# NEWSWEEP.net
KiCad netlist of a schematic drawn in Altium Designer
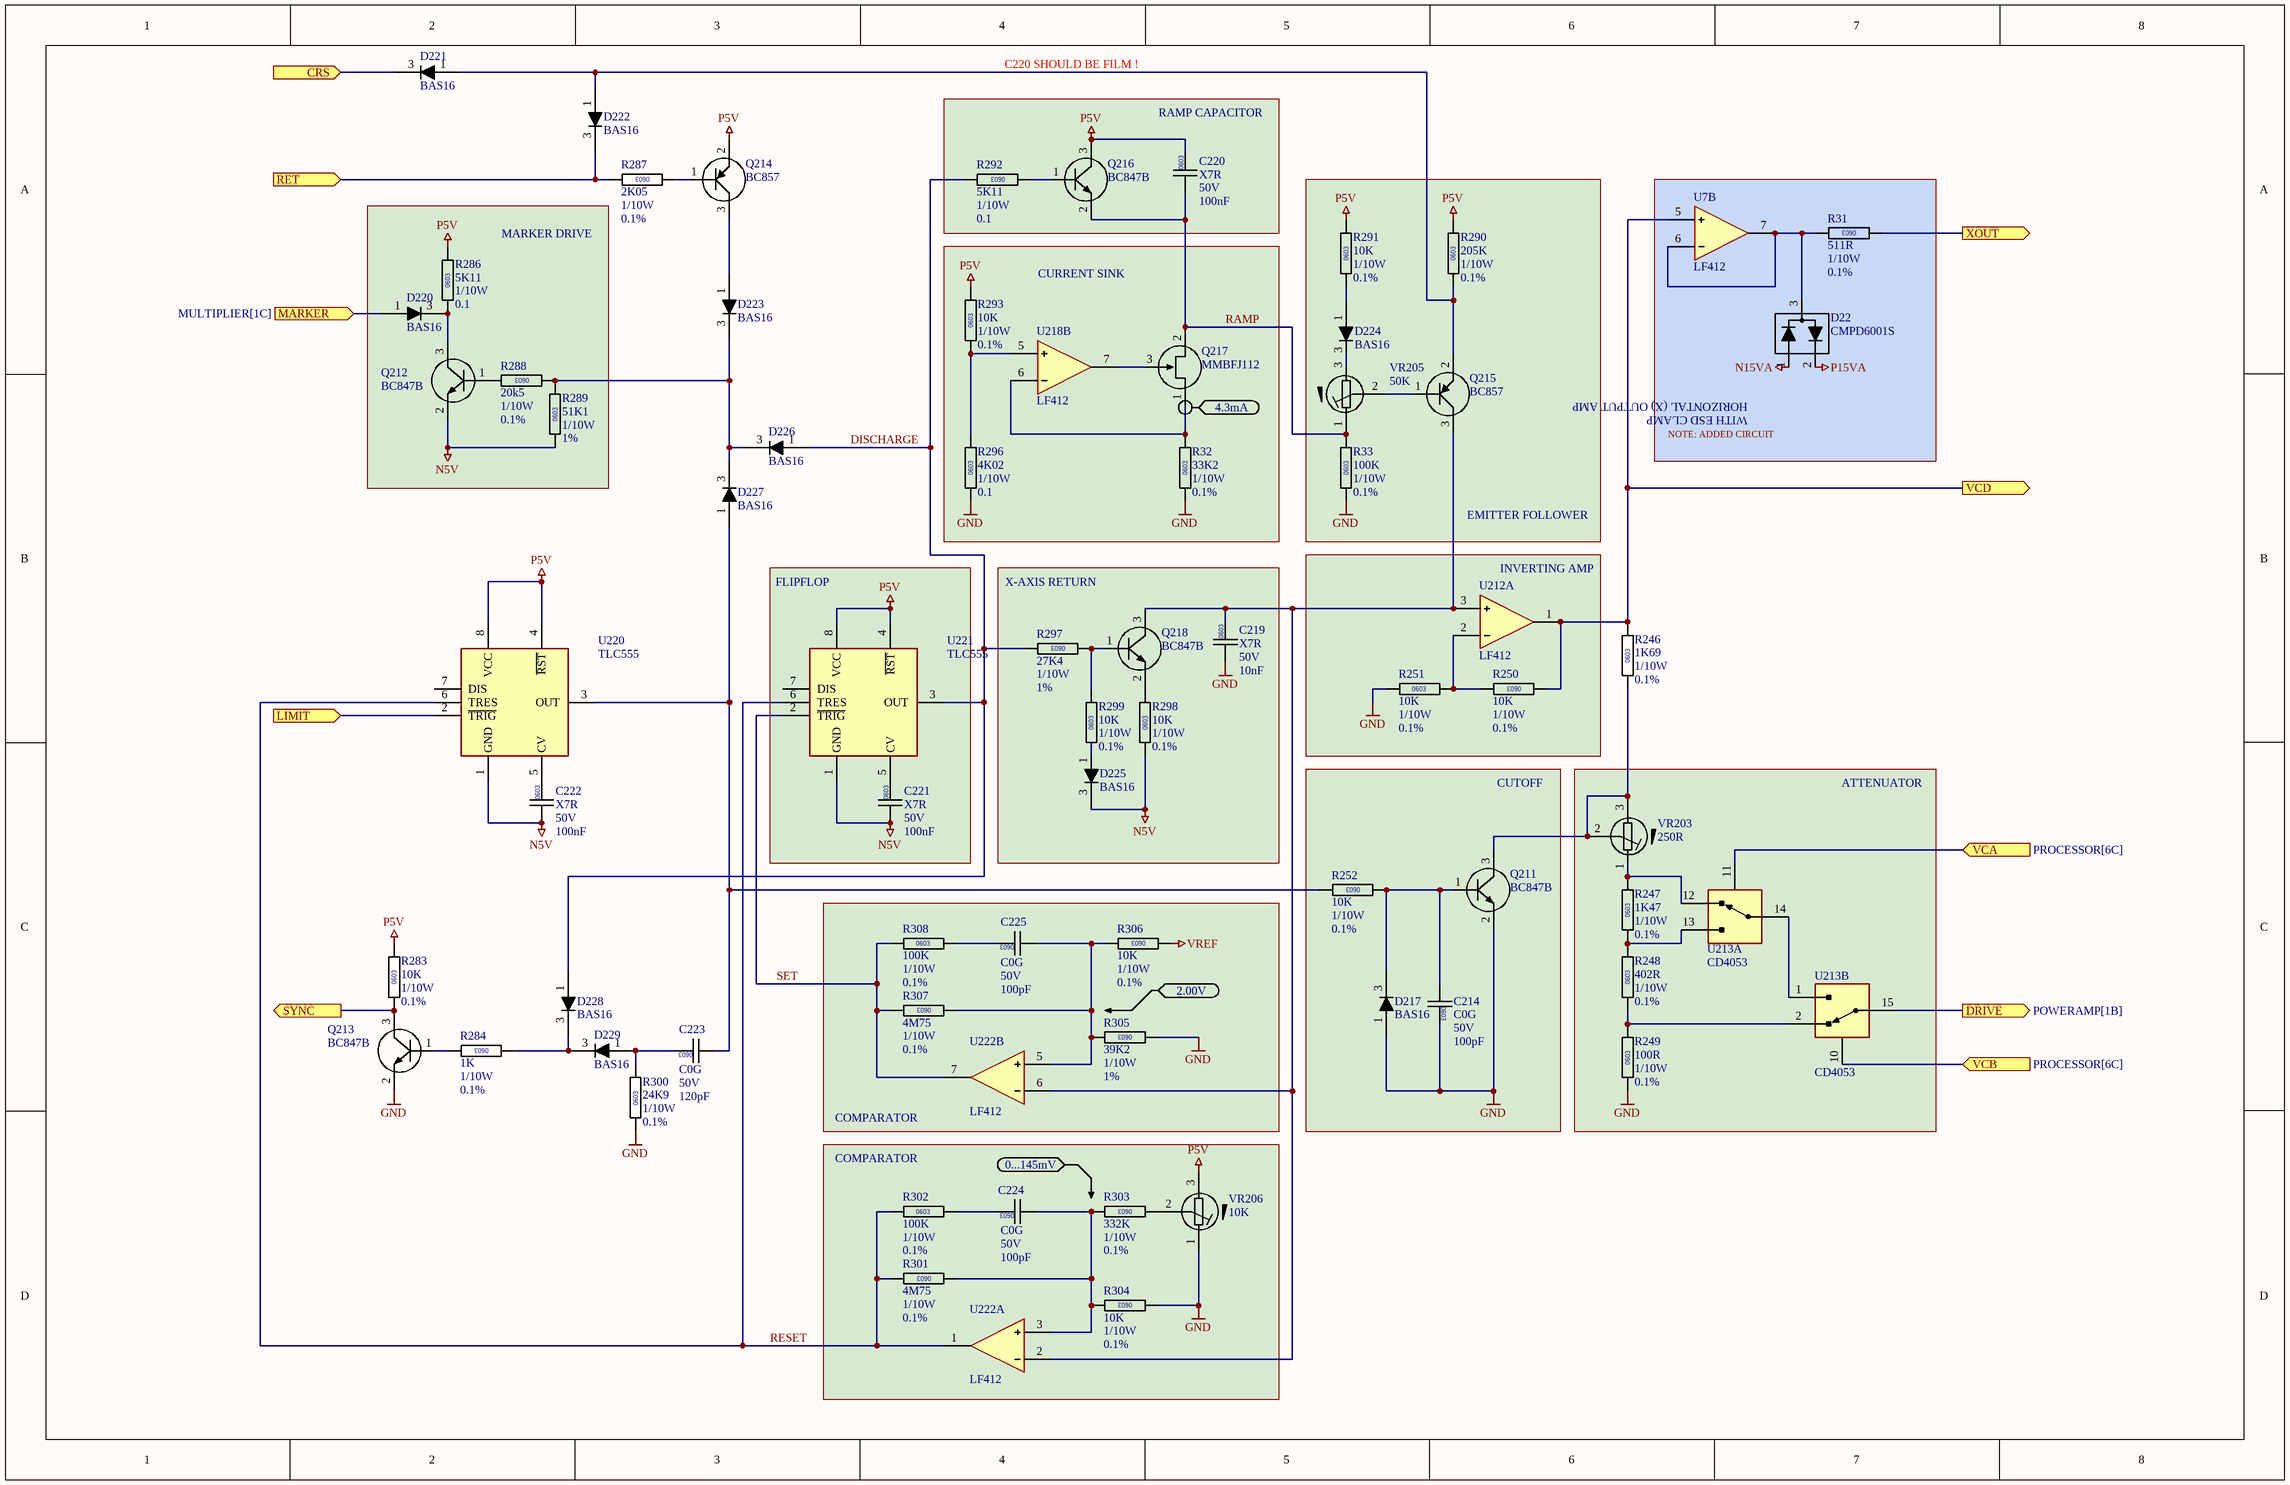
[diagram p0: NEWSWEEP.SchDoc]

(export (version "E")
  (design (tool "Eeschema 10.0.6"))
  (components
    (comp (ref "C214")
      (value "CAP0603")
      (footprint "CAPC0603")
      (description "CAPACITOR,CERAMIC,100pF,50V,C0G,0603")
      (fields
        (field (name "DIELECTRIC") "C0G")
        (field (name "VOLTAGE") "50V")
        (field (name "CAPACITANCE") "100pF")
      )
      (libsource (lib "CAPACITORS") (part "CAPC-0603-100pF-50V-C0G"))
    )
    (comp (ref "C219")
      (value "CAP0603")
      (footprint "CAPC0603")
      (description "CAPACITOR,CERAMIC,10nF,50V,X7R,0603")
      (fields
        (field (name "DIELECTRIC") "X7R")
        (field (name "VOLTAGE") "50V")
        (field (name "CAPACITANCE") "10nF")
      )
      (libsource (lib "CAPACITORS") (part "CAPC-0603-10nF-50V-X7R"))
    )
    (comp (ref "C220")
      (value "CAP0603")
      (footprint "CAPC0603")
      (description "CAPACITOR,CERAMIC,100nF,50V,X7R,0603")
      (fields
        (field (name "DIELECTRIC") "X7R")
        (field (name "VOLTAGE") "50V")
        (field (name "CAPACITANCE") "100nF")
      )
      (libsource (lib "CAPACITORS") (part "CAPC-0603-100nF-50V-X7R"))
    )
    (comp (ref "C221")
      (value "CAP0603")
      (footprint "CAPC0603")
      (description "CAPACITOR,CERAMIC,100nF,50V,X7R,0603")
      (fields
        (field (name "DIELECTRIC") "X7R")
        (field (name "VOLTAGE") "50V")
        (field (name "CAPACITANCE") "100nF")
      )
      (libsource (lib "CAPACITORS") (part "CAPC-0603-100nF-50V-X7R"))
    )
    (comp (ref "C222")
      (value "CAP0603")
      (footprint "CAPC0603")
      (description "CAPACITOR,CERAMIC,100nF,50V,X7R,0603")
      (fields
        (field (name "DIELECTRIC") "X7R")
        (field (name "VOLTAGE") "50V")
        (field (name "CAPACITANCE") "100nF")
      )
      (libsource (lib "CAPACITORS") (part "CAPC-0603-100nF-50V-X7R"))
    )
    (comp (ref "C223")
      (value "CAP0603")
      (footprint "CAPC0603")
      (description "CAPACITOR,CERAMIC,120pF,50V,C0G,0603")
      (fields
        (field (name "DIELECTRIC") "C0G")
        (field (name "VOLTAGE") "50V")
        (field (name "CAPACITANCE") "120pF")
      )
      (libsource (lib "CAPACITORS") (part "CAPC-0603-120pF-50V-C0G"))
    )
    (comp (ref "C224")
      (value "CAP0603")
      (footprint "CAPC0603")
      (description "CAPACITOR,CERAMIC,100pF,50V,C0G,0603")
      (fields
        (field (name "DIELECTRIC") "C0G")
        (field (name "VOLTAGE") "50V")
        (field (name "CAPACITANCE") "100pF")
      )
      (libsource (lib "CAPACITORS") (part "CAPC-0603-100pF-50V-C0G"))
    )
    (comp (ref "C225")
      (value "CAP0603")
      (footprint "CAPC0603")
      (description "CAPACITOR,CERAMIC,100pF,50V,C0G,0603")
      (fields
        (field (name "DIELECTRIC") "C0G")
        (field (name "VOLTAGE") "50V")
        (field (name "CAPACITANCE") "100pF")
      )
      (libsource (lib "CAPACITORS") (part "CAPC-0603-100pF-50V-C0G"))
    )
    (comp (ref "D22")
      (value "CMPD6001S")
      (footprint "SOT23")
      (description "DIODE,75V,250mA,SOT23,500pA ULTRA LOW LEAKAGE")
      (libsource (lib "DIODES") (part "DIODE-CENTRALSEMI-CMPD6001S"))
    )
    (comp (ref "D217")
      (value "BAS16")
      (description "DIODE,RECTIFIER,75V,0.3A,BAS16,SOT23")
      (libsource (lib "DIODES") (part "DIODE-RECTIFIER-DIODES-BAS16-SOT23"))
    )
    (comp (ref "D220")
      (value "BAS16")
      (description "DIODE,RECTIFIER,75V,0.3A,BAS16,SOT23")
      (libsource (lib "DIODES") (part "DIODE-RECTIFIER-DIODES-BAS16-SOT23"))
    )
    (comp (ref "D221")
      (value "BAS16")
      (description "DIODE,RECTIFIER,75V,0.3A,BAS16,SOT23")
      (libsource (lib "DIODES") (part "DIODE-RECTIFIER-DIODES-BAS16-SOT23"))
    )
    (comp (ref "D222")
      (value "BAS16")
      (description "DIODE,RECTIFIER,75V,0.3A,BAS16,SOT23")
      (libsource (lib "DIODES") (part "DIODE-RECTIFIER-DIODES-BAS16-SOT23"))
    )
    (comp (ref "D223")
      (value "BAS16")
      (description "DIODE,RECTIFIER,75V,0.3A,BAS16,SOT23")
      (libsource (lib "DIODES") (part "DIODE-RECTIFIER-DIODES-BAS16-SOT23"))
    )
    (comp (ref "D224")
      (value "BAS16")
      (description "DIODE,RECTIFIER,75V,0.3A,BAS16,SOT23")
      (libsource (lib "DIODES") (part "DIODE-RECTIFIER-DIODES-BAS16-SOT23"))
    )
    (comp (ref "D225")
      (value "BAS16")
      (description "DIODE,RECTIFIER,75V,0.3A,BAS16,SOT23")
      (libsource (lib "DIODES") (part "DIODE-RECTIFIER-DIODES-BAS16-SOT23"))
    )
    (comp (ref "D226")
      (value "BAS16")
      (description "DIODE,RECTIFIER,75V,0.3A,BAS16,SOT23")
      (libsource (lib "DIODES") (part "DIODE-RECTIFIER-DIODES-BAS16-SOT23"))
    )
    (comp (ref "D227")
      (value "BAS16")
      (description "DIODE,RECTIFIER,75V,0.3A,BAS16,SOT23")
      (libsource (lib "DIODES") (part "DIODE-RECTIFIER-DIODES-BAS16-SOT23"))
    )
    (comp (ref "D228")
      (value "BAS16")
      (description "DIODE,RECTIFIER,75V,0.3A,BAS16,SOT23")
      (libsource (lib "DIODES") (part "DIODE-RECTIFIER-DIODES-BAS16-SOT23"))
    )
    (comp (ref "D229")
      (value "BAS16")
      (description "DIODE,RECTIFIER,75V,0.3A,BAS16,SOT23")
      (libsource (lib "DIODES") (part "DIODE-RECTIFIER-DIODES-BAS16-SOT23"))
    )
    (comp (ref "Q211")
      (value "BC847B")
      (footprint "SOT23")
      (description "XSTR,NPN,45V,0.1A,,BC847B,SOT23")
      (libsource (lib "TRANSISTORS") (part "XSTR-NPN-BC847"))
    )
    (comp (ref "Q212")
      (value "BC847B")
      (footprint "SOT23")
      (description "XSTR,NPN,45V,0.1A,,BC847B,SOT23")
      (libsource (lib "TRANSISTORS") (part "XSTR-NPN-BC847"))
    )
    (comp (ref "Q213")
      (value "BC847B")
      (footprint "SOT23")
      (description "XSTR,NPN,45V,0.1A,,BC847B,SOT23")
      (libsource (lib "TRANSISTORS") (part "XSTR-NPN-BC847"))
    )
    (comp (ref "Q214")
      (value "BC857")
      (footprint "SOT23")
      (description "XSTR,PNP,SOT23,BC857,SOT23")
      (libsource (lib "TRANSISTORS") (part "XSTR-PNP-BC857"))
    )
    (comp (ref "Q215")
      (value "BC857")
      (footprint "SOT23")
      (description "XSTR,PNP,SOT23,BC857,SOT23")
      (libsource (lib "TRANSISTORS") (part "XSTR-PNP-BC857"))
    )
    (comp (ref "Q216")
      (value "BC847B")
      (footprint "SOT23")
      (description "XSTR,NPN,45V,0.1A,,BC847B,SOT23")
      (libsource (lib "TRANSISTORS") (part "XSTR-NPN-BC847"))
    )
    (comp (ref "Q217")
      (value "MMBFJ112")
      (description "XSTR,JFET,NCHAN,ONSEMI,MMBFJ112,SOT23")
      (libsource (lib "TRANSISTORS") (part "XSTR-ONSEMI-J112-SOT23"))
    )
    (comp (ref "Q218")
      (value "BC847B")
      (footprint "SOT23")
      (description "XSTR,NPN,45V,0.1A,,BC847B,SOT23")
      (libsource (lib "TRANSISTORS") (part "XSTR-NPN-BC847"))
    )
    (comp (ref "R31")
      (value "511R")
      (footprint "RESC0603")
      (description "RESISTOR,511R,0.1%,100mW,0603 (1608)")
      (fields
        (field (name "POWER") "1/10W")
        (field (name "TOLERANCE") "0.1%")
        (field (name "Comment") "RESC0603")
      )
      (libsource (lib "RESISTORS") (part "RESC-0603-511R-0.1%"))
    )
    (comp (ref "R32")
      (value "33K2")
      (footprint "RESC0603")
      (description "RESISTOR,33K2,0.1%,100mW,0603 (1608)")
      (fields
        (field (name "POWER") "1/10W")
        (field (name "TOLERANCE") "0.1%")
        (field (name "Comment") "RESC0603")
      )
      (libsource (lib "RESISTORS") (part "RESC-0603-33K2-0.1%-1/10W"))
    )
    (comp (ref "R33")
      (value "100K")
      (footprint "RESC0603")
      (description "RESISTOR,100K,0.1%,100mW,0603 (1608)")
      (fields
        (field (name "POWER") "1/10W")
        (field (name "TOLERANCE") "0.1%")
        (field (name "Comment") "RESC0603")
      )
      (libsource (lib "RESISTORS") (part "RESC-0603-100K-0.1%-1/10W"))
    )
    (comp (ref "R246")
      (value "1K69")
      (footprint "RESC0603")
      (description "RESISTOR,1K69,0.1%,100mW,0603 (1608)")
      (fields
        (field (name "POWER") "1/10W")
        (field (name "TOLERANCE") "0.1%")
        (field (name "Comment") "RESC0603")
      )
      (libsource (lib "RESISTORS") (part "RESC-0603-1K69-0.1%-1/10W"))
    )
    (comp (ref "R247")
      (value "1K47")
      (footprint "RESC0603")
      (description "RESISTOR,1K47,0.1%,100mW,0603 (1608)")
      (fields
        (field (name "POWER") "1/10W")
        (field (name "TOLERANCE") "0.1%")
        (field (name "Comment") "RESC0603")
      )
      (libsource (lib "RESISTORS") (part "RESC-0603-1K47-0.1%-1/10W"))
    )
    (comp (ref "R248")
      (value "402R")
      (footprint "RESC0603")
      (description "RESISTOR,402R,0.1%,100mW,0603 (1608)")
      (fields
        (field (name "POWER") "1/10W")
        (field (name "TOLERANCE") "0.1%")
        (field (name "Comment") "RESC0603")
      )
      (libsource (lib "RESISTORS") (part "RESC-0603-402R-0.1%-1/10W"))
    )
    (comp (ref "R249")
      (value "100R")
      (footprint "RESC0603")
      (description "RESISTOR,100R,0.1%,100mW,0603 (1608)")
      (fields
        (field (name "POWER") "1/10W")
        (field (name "TOLERANCE") "0.1%")
        (field (name "Comment") "RESC0603")
      )
      (libsource (lib "RESISTORS") (part "RESC-0603-100R,0.1%-1/10W"))
    )
    (comp (ref "R250")
      (value "10K")
      (footprint "RESC0603")
      (description "RESISTOR,10K,0.1%,100mW,0603 (1608)")
      (fields
        (field (name "POWER") "1/10W")
        (field (name "TOLERANCE") "0.1%")
        (field (name "Comment") "RESC0603")
      )
      (libsource (lib "RESISTORS") (part "RESC-0603-10K-0.1%-1/10W"))
    )
    (comp (ref "R251")
      (value "10K")
      (footprint "RESC0603")
      (description "RESISTOR,10K,0.1%,100mW,0603 (1608)")
      (fields
        (field (name "POWER") "1/10W")
        (field (name "TOLERANCE") "0.1%")
        (field (name "Comment") "RESC0603")
      )
      (libsource (lib "RESISTORS") (part "RESC-0603-10K-0.1%-1/10W"))
    )
    (comp (ref "R252")
      (value "10K")
      (footprint "RESC0603")
      (description "RESISTOR,10K,0.1%,100mW,0603 (1608)")
      (fields
        (field (name "POWER") "1/10W")
        (field (name "TOLERANCE") "0.1%")
        (field (name "Comment") "RESC0603")
      )
      (libsource (lib "RESISTORS") (part "RESC-0603-10K-0.1%-1/10W"))
    )
    (comp (ref "R283")
      (value "10K")
      (footprint "RESC0603")
      (description "RESISTOR,10K,0.1%,100mW,0603 (1608)")
      (fields
        (field (name "POWER") "1/10W")
        (field (name "TOLERANCE") "0.1%")
        (field (name "Comment") "RESC0603")
      )
      (libsource (lib "RESISTORS") (part "RESC-0603-10K-0.1%-1/10W"))
    )
    (comp (ref "R284")
      (value "1K")
      (footprint "RESC0603")
      (description "RESISTOR,1K,0.1%,100mW,0603 (1608)")
      (fields
        (field (name "POWER") "1/10W")
        (field (name "TOLERANCE") "0.1%")
        (field (name "Comment") "RESC0603")
      )
      (libsource (lib "RESISTORS") (part "RESC-0603-1K-0.1%-1/10W"))
    )
    (comp (ref "R286")
      (value "5K11")
      (footprint "RESC0603")
      (description "RESISTOR,5K11,0.1%,100mW,0603 (1608)")
      (fields
        (field (name "POWER") "1/10W")
        (field (name "TOLERANCE") "0.1")
        (field (name "Comment") "RESC0603")
      )
      (libsource (lib "RESISTORS") (part "RESC-0603-5K11-0.1%-1/10W"))
    )
    (comp (ref "R287")
      (value "2K05")
      (footprint "RESC0603")
      (description "RESISTOR,2K05,0.11%,100mW,0603 (1608)")
      (fields
        (field (name "POWER") "1/10W")
        (field (name "TOLERANCE") "0.1%")
        (field (name "Comment") "RESC0603")
      )
      (libsource (lib "RESISTORS") (part "RESC-0603-2K05-0.1%-1/10W"))
    )
    (comp (ref "R288")
      (value "20k5")
      (footprint "RESC0603")
      (description "RESISTOR,20K5,0.1%,100mW,0603 (1608)")
      (fields
        (field (name "POWER") "1/10W")
        (field (name "TOLERANCE") "0.1%")
        (field (name "Comment") "RESC0603")
      )
      (libsource (lib "RESISTORS") (part "RESC-0603-20K5-0.1%-1/10W"))
    )
    (comp (ref "R289")
      (value "51K1")
      (footprint "RESC0603")
      (description "RESISTOR,51K1,1%,100mW,0603 (1608)")
      (fields
        (field (name "POWER") "1/10W")
        (field (name "TOLERANCE") "1%")
        (field (name "Comment") "RESC0603")
      )
      (libsource (lib "RESISTORS") (part "RESC-0603-51K1-1%-1/10W"))
    )
    (comp (ref "R290")
      (value "205K")
      (footprint "RESC0603")
      (description "RESISTOR,205K,0.1%,100mW,0603 (1608)")
      (fields
        (field (name "POWER") "1/10W")
        (field (name "TOLERANCE") "0.1%")
        (field (name "Comment") "RESC0603")
      )
      (libsource (lib "RESISTORS") (part "RESC-0603-205K-0.1%-1/10W"))
    )
    (comp (ref "R291")
      (value "10K")
      (footprint "RESC0603")
      (description "RESISTOR,10K,0.1%,100mW,0603 (1608)")
      (fields
        (field (name "POWER") "1/10W")
        (field (name "TOLERANCE") "0.1%")
        (field (name "Comment") "RESC0603")
      )
      (libsource (lib "RESISTORS") (part "RESC-0603-10K-0.1%-1/10W"))
    )
    (comp (ref "R292")
      (value "5K11")
      (footprint "RESC0603")
      (description "RESISTOR,5K11,0.1%,100mW,0603 (1608)")
      (fields
        (field (name "POWER") "1/10W")
        (field (name "TOLERANCE") "0.1")
        (field (name "Comment") "RESC0603")
      )
      (libsource (lib "RESISTORS") (part "RESC-0603-5K11-0.1%-1/10W"))
    )
    (comp (ref "R293")
      (value "10K")
      (footprint "RESC0603")
      (description "RESISTOR,10K,0.1%,100mW,0603 (1608)")
      (fields
        (field (name "POWER") "1/10W")
        (field (name "TOLERANCE") "0.1%")
        (field (name "Comment") "RESC0603")
      )
      (libsource (lib "RESISTORS") (part "RESC-0603-10K-0.1%-1/10W"))
    )
    (comp (ref "R296")
      (value "4K02")
      (footprint "RESC0603")
      (description "RESISTOR,4K02,0.1%,100mW,0603 (1608)")
      (fields
        (field (name "POWER") "1/10W")
        (field (name "TOLERANCE") "0.1")
        (field (name "Comment") "RESC0603")
      )
      (libsource (lib "RESISTORS") (part "RESC-0603-4K02-0.1%-1/10W"))
    )
    (comp (ref "R297")
      (value "27K4")
      (footprint "RESC0603")
      (description "RESISTOR,27K4,1%,100mW,0603 (1608)")
      (fields
        (field (name "POWER") "1/10W")
        (field (name "TOLERANCE") "1%")
        (field (name "Comment") "RESC0603")
      )
      (libsource (lib "RESISTORS") (part "RESC-0603-27K4-1%-1/10W"))
    )
    (comp (ref "R298")
      (value "10K")
      (footprint "RESC0603")
      (description "RESISTOR,10K,0.1%,100mW,0603 (1608)")
      (fields
        (field (name "POWER") "1/10W")
        (field (name "TOLERANCE") "0.1%")
        (field (name "Comment") "RESC0603")
      )
      (libsource (lib "RESISTORS") (part "RESC-0603-10K-0.1%-1/10W"))
    )
    (comp (ref "R299")
      (value "10K")
      (footprint "RESC0603")
      (description "RESISTOR,10K,0.1%,100mW,0603 (1608)")
      (fields
        (field (name "POWER") "1/10W")
        (field (name "TOLERANCE") "0.1%")
        (field (name "Comment") "RESC0603")
      )
      (libsource (lib "RESISTORS") (part "RESC-0603-10K-0.1%-1/10W"))
    )
    (comp (ref "R300")
      (value "24K9")
      (footprint "RESC0603")
      (description "RESISTOR,24K9,0.1%,100mW,0603 (1608)")
      (fields
        (field (name "POWER") "1/10W")
        (field (name "TOLERANCE") "0.1%")
        (field (name "Comment") "RESC0603")
      )
      (libsource (lib "RESISTORS") (part "RESC-0603-24K9-0.1%-1/10W"))
    )
    (comp (ref "R301")
      (value "4M75")
      (footprint "RESC0603")
      (description "RESISTOR,4M75,0.1%,100mW,0603 (1608)")
      (fields
        (field (name "POWER") "1/10W")
        (field (name "TOLERANCE") "0.1%")
        (field (name "Comment") "RESC0603")
      )
      (libsource (lib "RESISTORS") (part "RESC-0603-4M75-1%-1/10W"))
    )
    (comp (ref "R302")
      (value "100K")
      (footprint "RESC0603")
      (description "RESISTOR,100K,0.1%,100mW,0603 (1608)")
      (fields
        (field (name "POWER") "1/10W")
        (field (name "TOLERANCE") "0.1%")
        (field (name "Comment") "RESC0603")
      )
      (libsource (lib "RESISTORS") (part "RESC-0603-100K-0.1%-1/10W"))
    )
    (comp (ref "R303")
      (value "332K")
      (footprint "RESC0603")
      (description "RESISTOR,332K,0.1%,100mW,0603 (1608)")
      (fields
        (field (name "POWER") "1/10W")
        (field (name "TOLERANCE") "0.1%")
        (field (name "Comment") "RESC0603")
      )
      (libsource (lib "RESISTORS") (part "RESC-0603-332K-0.1%-1/10W"))
    )
    (comp (ref "R304")
      (value "10K")
      (footprint "RESC0603")
      (description "RESISTOR,10K,0.1%,100mW,0603 (1608)")
      (fields
        (field (name "POWER") "1/10W")
        (field (name "TOLERANCE") "0.1%")
        (field (name "Comment") "RESC0603")
      )
      (libsource (lib "RESISTORS") (part "RESC-0603-10K-0.1%-1/10W"))
    )
    (comp (ref "R305")
      (value "39K2")
      (footprint "RESC0603")
      (description "RESISTOR,39K2,0.1%,100mW,0603 (1608)")
      (fields
        (field (name "POWER") "1/10W")
        (field (name "TOLERANCE") "1%")
        (field (name "Comment") "RESC0603")
      )
      (libsource (lib "RESISTORS") (part "RESC-0603-39K2-0.1%-1/10W"))
    )
    (comp (ref "R306")
      (value "10K")
      (footprint "RESC0603")
      (description "RESISTOR,10K,0.1%,100mW,0603 (1608)")
      (fields
        (field (name "POWER") "1/10W")
        (field (name "TOLERANCE") "0.1%")
        (field (name "Comment") "RESC0603")
      )
      (libsource (lib "RESISTORS") (part "RESC-0603-10K-0.1%-1/10W"))
    )
    (comp (ref "R307")
      (value "4M75")
      (footprint "RESC0603")
      (description "RESISTOR,4M75,0.1%,100mW,0603 (1608)")
      (fields
        (field (name "POWER") "1/10W")
        (field (name "TOLERANCE") "0.1%")
        (field (name "Comment") "RESC0603")
      )
      (libsource (lib "RESISTORS") (part "RESC-0603-4M75-1%-1/10W"))
    )
    (comp (ref "R308")
      (value "100K")
      (footprint "RESC0603")
      (description "RESISTOR,100K,0.1%,100mW,0603 (1608)")
      (fields
        (field (name "POWER") "1/10W")
        (field (name "TOLERANCE") "0.1%")
        (field (name "Comment") "RESC0603")
      )
      (libsource (lib "RESISTORS") (part "RESC-0603-100K-0.1%-1/10W"))
    )
    (comp (ref "U7")
      (value "LF412")
      (footprint "SO127P600-8N")
      (description "IC,OPAMP JFET,DUAL,LF412,SO8")
      (libsource (lib "") (part "IC-TI-LF412-S08_1"))
    )
    (comp (ref "U212")
      (value "LF412")
      (footprint "SO127P600-8N")
      (description "IC,OPAMP JFET,DUAL,LF412,SO8")
      (libsource (lib "") (part "IC-TI-LF412-S08_1"))
    )
    (comp (ref "U213")
      (value "CD4053")
      (footprint "SO127P600-16N")
      (description "IC,MUX,TRIPLE 2:1 MUX,SPLIT BLOCKS")
      (libsource (lib "") (part "IC-TI-CD4053-SPLIT_1"))
    )
    (comp (ref "U218")
      (value "LF412")
      (footprint "SO127P600-8N")
      (description "IC,OPAMP JFET,DUAL,LF412,SO8")
      (libsource (lib "") (part "IC-TI-LF412-S08_1"))
    )
    (comp (ref "U220")
      (value "TLC555")
      (footprint "SO127P600-8N")
      (description "IC,TIMER,CMOSE,TI,TLC555,SO8")
      (libsource (lib "IC-TIMING") (part "IC-TI-TLC555-SO8"))
    )
    (comp (ref "U221")
      (value "TLC555")
      (footprint "SO127P600-8N")
      (description "IC,TIMER,CMOSE,TI,TLC555,SO8")
      (libsource (lib "IC-TIMING") (part "IC-TI-TLC555-SO8"))
    )
    (comp (ref "U222")
      (value "LF412")
      (footprint "SO127P600-8N")
      (description "IC,OPAMP JFET,DUAL,LF412,SO8")
      (libsource (lib "IC-OPAMP") (part "IC-TI-LF412-S08"))
    )
    (comp (ref "VR203")
      (value "250R")
      (footprint "TRIMMER-BOURNS-3214X")
      (description "RESISTOR,MULTITURN,VERTICAL,5T,250R")
      (fields (field (name "Comment") "TRIMMER-BOURNS-3214X-1-251"))
      (libsource (lib "RESISTORS") (part "TRIMMER-BOURNS-3214X-1-251"))
    )
    (comp (ref "VR205")
      (value "50K")
      (footprint "TRIMMER-BOURNS-3214X")
      (description "RESISTOR,MULTITURN,VERTICAL,5T,50K")
      (fields (field (name "Comment") "TRIMMER-BOURNS-3214X-1-503"))
      (libsource (lib "RESISTORS") (part "TRIMMER-BOURNS-3214X-1-503"))
    )
    (comp (ref "VR206")
      (value "10K")
      (footprint "TRIMMER-BOURNS-3214X")
      (description "RESISTOR,MULTITURN,VERTICAL,5T,10K")
      (fields (field (name "Comment") "TRIMMER-BOURNS-3214X-1-103E"))
      (libsource (lib "RESISTORS") (part "TRIMMER-BOURNS-3214X-1-103E"))
    )
  )
  (nets
    (net (code "1") (name "/CRS") (class "Default")
      (node (ref "D221") (pin "3") (pinfunction "K_3") (pintype "passive"))
    )
    (net (code "2") (name "/DISCHARGE") (class "Default")
      (node (ref "D226") (pin "1") (pinfunction "A_1") (pintype "passive"))
      (node (ref "D228") (pin "1") (pinfunction "A_1") (pintype "passive"))
      (node (ref "R292") (pin "2") (pintype "passive"))
      (node (ref "R297") (pin "1") (pintype "passive"))
      (node (ref "U221") (pin "3") (pinfunction "OUT_3") (pintype "passive"))
    )
    (net (code "3") (name "/DRIVE") (class "Default")
      (node (ref "U213") (pin "15") (pinfunction "X2_15") (pintype "passive"))
    )
    (net (code "4") (name "/LIMIT") (class "Default")
      (node (ref "U220") (pin "2") (pinfunction "~{TRIG}_2") (pintype "passive"))
    )
    (net (code "5") (name "/MARKER") (class "Default")
      (node (ref "D220") (pin "1") (pinfunction "A_1") (pintype "passive"))
    )
    (net (code "6") (name "/RAMP") (class "Default")
      (node (ref "C220") (pin "2") (pintype "passive"))
      (node (ref "Q216") (pin "2") (pinfunction "E_2") (pintype "passive"))
      (node (ref "Q217") (pin "2") (pinfunction "S_2") (pintype "passive"))
      (node (ref "R33") (pin "1") (pintype "passive"))
      (node (ref "VR205") (pin "1") (pinfunction "1_1") (pintype "passive"))
    )
    (net (code "7") (name "/RESET") (class "Default")
      (node (ref "R301") (pin "1") (pintype "passive"))
      (node (ref "R302") (pin "1") (pintype "passive"))
      (node (ref "U220") (pin "6") (pinfunction "TRES_6") (pintype "passive"))
      (node (ref "U221") (pin "6") (pinfunction "TRES_6") (pintype "passive"))
      (node (ref "U222") (pin "1") (pinfunction "O_1") (pintype "passive"))
    )
    (net (code "8") (name "/RET") (class "Default")
      (node (ref "D222") (pin "3") (pinfunction "K_3") (pintype "passive"))
      (node (ref "R287") (pin "1") (pintype "passive"))
    )
    (net (code "9") (name "/SET") (class "Default")
      (node (ref "R307") (pin "1") (pintype "passive"))
      (node (ref "R308") (pin "1") (pintype "passive"))
      (node (ref "U221") (pin "2") (pinfunction "~{TRIG}_2") (pintype "passive"))
      (node (ref "U222") (pin "7") (pinfunction "O_7") (pintype "passive"))
    )
    (net (code "10") (name "/SYNC") (class "Default")
      (node (ref "Q213") (pin "3") (pinfunction "C_3") (pintype "passive"))
      (node (ref "R283") (pin "2") (pintype "passive"))
    )
    (net (code "11") (name "/VCA") (class "Default")
      (node (ref "U213") (pin "11") (pinfunction "X3_11") (pintype "passive"))
    )
    (net (code "12") (name "/VCB") (class "Default")
      (node (ref "U213") (pin "10") (pinfunction "A_10") (pintype "passive"))
    )
    (net (code "13") (name "/VCD") (class "Default")
      (node (ref "R246") (pin "1") (pintype "passive"))
      (node (ref "R250") (pin "2") (pintype "passive"))
      (node (ref "U212") (pin "1") (pinfunction "O_1") (pintype "passive"))
      (node (ref "U7") (pin "5") (pinfunction "+_5") (pintype "passive"))
    )
    (net (code "14") (name "/XOUT") (class "Default") (node (ref "R31") (pin "2") (pintype "passive")))
    (net (code "15") (name "GND") (class "Default")
      (node (ref "C214") (pin "1") (pintype "passive"))
      (node (ref "C219") (pin "2") (pintype "passive"))
      (node (ref "D217") (pin "1") (pinfunction "A_1") (pintype "passive"))
      (node (ref "Q211") (pin "2") (pinfunction "E_2") (pintype "passive"))
      (node (ref "Q213") (pin "2") (pinfunction "E_2") (pintype "passive"))
      (node (ref "R249") (pin "2") (pintype "passive"))
      (node (ref "R251") (pin "2") (pintype "passive"))
      (node (ref "R296") (pin "2") (pintype "passive"))
      (node (ref "R300") (pin "2") (pintype "passive"))
      (node (ref "R304") (pin "2") (pintype "passive"))
      (node (ref "R305") (pin "2") (pintype "passive"))
      (node (ref "R32") (pin "2") (pintype "passive"))
      (node (ref "R33") (pin "2") (pintype "passive"))
      (node (ref "VR206") (pin "1") (pinfunction "1_1") (pintype "passive"))
    )
    (net (code "16") (name "N5V") (class "Default")
      (node (ref "C221") (pin "2") (pintype "passive"))
      (node (ref "C222") (pin "2") (pintype "passive"))
      (node (ref "D225") (pin "3") (pinfunction "K_3") (pintype "passive"))
      (node (ref "Q212") (pin "2") (pinfunction "E_2") (pintype "passive"))
      (node (ref "R289") (pin "2") (pintype "passive"))
      (node (ref "R298") (pin "2") (pintype "passive"))
      (node (ref "U220") (pin "1") (pinfunction "GND_1") (pintype "passive"))
      (node (ref "U221") (pin "1") (pinfunction "GND_1") (pintype "passive"))
    )
    (net (code "17") (name "N15VA") (class "Default")
      (node (ref "D22") (pin "1") (pinfunction "K_1") (pintype "passive"))
    )
    (net (code "18") (name "Net-(C224-Pad1)") (class "Default")
      (node (ref "C224") (pin "1") (pintype "passive"))
      (node (ref "R302") (pin "2") (pintype "passive"))
    )
    (net (code "19") (name "Net-(C225-Pad1)") (class "Default")
      (node (ref "C225") (pin "1") (pintype "passive"))
      (node (ref "R308") (pin "2") (pintype "passive"))
    )
    (net (code "20") (name "Net-(D217-K)") (class "Default")
      (node (ref "C214") (pin "2") (pintype "passive"))
      (node (ref "D217") (pin "3") (pinfunction "K_3") (pintype "passive"))
      (node (ref "Q211") (pin "1") (pinfunction "B_1") (pintype "passive"))
      (node (ref "R252") (pin "2") (pintype "passive"))
    )
    (net (code "21") (name "Net-(D220-K)") (class "Default")
      (node (ref "D220") (pin "3") (pinfunction "K_3") (pintype "passive"))
      (node (ref "Q212") (pin "3") (pinfunction "C_3") (pintype "passive"))
      (node (ref "R286") (pin "2") (pintype "passive"))
    )
    (net (code "22") (name "Net-(D221-A)") (class "Default")
      (node (ref "D221") (pin "1") (pinfunction "A_1") (pintype "passive"))
      (node (ref "D222") (pin "1") (pinfunction "A_1") (pintype "passive"))
      (node (ref "Q215") (pin "2") (pinfunction "E_2") (pintype "passive"))
      (node (ref "R290") (pin "2") (pintype "passive"))
    )
    (net (code "23") (name "Net-(D223-A)") (class "Default")
      (node (ref "D223") (pin "1") (pinfunction "A_1") (pintype "passive"))
      (node (ref "Q214") (pin "3") (pinfunction "C_3") (pintype "passive"))
    )
    (net (code "24") (name "Net-(D223-K)") (class "Default")
      (node (ref "D223") (pin "3") (pinfunction "K_3") (pintype "passive"))
      (node (ref "D226") (pin "3") (pinfunction "K_3") (pintype "passive"))
      (node (ref "D227") (pin "3") (pinfunction "K_3") (pintype "passive"))
      (node (ref "R288") (pin "2") (pintype "passive"))
      (node (ref "R289") (pin "1") (pintype "passive"))
    )
    (net (code "25") (name "Net-(D224-A)") (class "Default")
      (node (ref "D224") (pin "1") (pinfunction "A_1") (pintype "passive"))
      (node (ref "R291") (pin "2") (pintype "passive"))
    )
    (net (code "26") (name "Net-(D224-K)") (class "Default")
      (node (ref "D224") (pin "3") (pinfunction "K_3") (pintype "passive"))
      (node (ref "VR205") (pin "3") (pinfunction "3_3") (pintype "passive"))
    )
    (net (code "27") (name "Net-(D225-A)") (class "Default")
      (node (ref "D225") (pin "1") (pinfunction "A_1") (pintype "passive"))
      (node (ref "R299") (pin "2") (pintype "passive"))
    )
    (net (code "28") (name "Net-(D227-A)") (class "Default")
      (node (ref "C223") (pin "2") (pintype "passive"))
      (node (ref "D227") (pin "1") (pinfunction "A_1") (pintype "passive"))
      (node (ref "R252") (pin "1") (pintype "passive"))
      (node (ref "U220") (pin "3") (pinfunction "OUT_3") (pintype "passive"))
    )
    (net (code "29") (name "Net-(D228-K)") (class "Default")
      (node (ref "D228") (pin "3") (pinfunction "K_3") (pintype "passive"))
      (node (ref "D229") (pin "3") (pinfunction "K_3") (pintype "passive"))
      (node (ref "R284") (pin "2") (pintype "passive"))
    )
    (net (code "30") (name "Net-(D229-A)") (class "Default")
      (node (ref "C223") (pin "1") (pintype "passive"))
      (node (ref "D229") (pin "1") (pinfunction "A_1") (pintype "passive"))
      (node (ref "R300") (pin "1") (pintype "passive"))
    )
    (net (code "31") (name "Net-(Q211-C)") (class "Default")
      (node (ref "Q211") (pin "3") (pinfunction "C_3") (pintype "passive"))
      (node (ref "R246") (pin "2") (pintype "passive"))
      (node (ref "VR203") (pin "2") (pinfunction "2_2") (pintype "passive"))
      (node (ref "VR203") (pin "3") (pinfunction "3_3") (pintype "passive"))
    )
    (net (code "32") (name "Net-(Q212-B)") (class "Default")
      (node (ref "Q212") (pin "1") (pinfunction "B_1") (pintype "passive"))
      (node (ref "R288") (pin "1") (pintype "passive"))
    )
    (net (code "33") (name "Net-(Q213-B)") (class "Default")
      (node (ref "Q213") (pin "1") (pinfunction "B_1") (pintype "passive"))
      (node (ref "R284") (pin "1") (pintype "passive"))
    )
    (net (code "34") (name "Net-(Q214-B)") (class "Default")
      (node (ref "Q214") (pin "1") (pinfunction "B_1") (pintype "passive"))
      (node (ref "R287") (pin "2") (pintype "passive"))
    )
    (net (code "35") (name "Net-(Q215-B)") (class "Default")
      (node (ref "Q215") (pin "1") (pinfunction "B_1") (pintype "passive"))
      (node (ref "VR205") (pin "2") (pinfunction "2_2") (pintype "passive"))
    )
    (net (code "36") (name "Net-(Q215-C)") (class "Default")
      (node (ref "C219") (pin "1") (pintype "passive"))
      (node (ref "Q215") (pin "3") (pinfunction "C_3") (pintype "passive"))
      (node (ref "Q218") (pin "3") (pinfunction "C_3") (pintype "passive"))
      (node (ref "U212") (pin "3") (pinfunction "+_3") (pintype "passive"))
      (node (ref "U222") (pin "2") (pinfunction "-_2") (pintype "passive"))
      (node (ref "U222") (pin "6") (pinfunction "-_6") (pintype "passive"))
    )
    (net (code "37") (name "Net-(Q216-B)") (class "Default")
      (node (ref "Q216") (pin "1") (pinfunction "B_1") (pintype "passive"))
      (node (ref "R292") (pin "1") (pintype "passive"))
    )
    (net (code "38") (name "Net-(Q217-D)") (class "Default")
      (node (ref "Q217") (pin "1") (pinfunction "D_1") (pintype "passive"))
      (node (ref "R32") (pin "1") (pintype "passive"))
      (node (ref "U218") (pin "6") (pinfunction "-_6") (pintype "passive"))
    )
    (net (code "39") (name "Net-(Q217-G)") (class "Default")
      (node (ref "Q217") (pin "3") (pinfunction "G_3") (pintype "passive"))
      (node (ref "U218") (pin "7") (pinfunction "O_7") (pintype "passive"))
    )
    (net (code "40") (name "Net-(Q218-B)") (class "Default")
      (node (ref "Q218") (pin "1") (pinfunction "B_1") (pintype "passive"))
      (node (ref "R297") (pin "2") (pintype "passive"))
      (node (ref "R299") (pin "1") (pintype "passive"))
    )
    (net (code "41") (name "Net-(Q218-E)") (class "Default")
      (node (ref "Q218") (pin "2") (pinfunction "E_2") (pintype "passive"))
      (node (ref "R298") (pin "1") (pintype "passive"))
    )
    (net (code "42") (name "Net-(R303-Pad2)") (class "Default")
      (node (ref "R303") (pin "2") (pintype "passive"))
      (node (ref "VR206") (pin "2") (pinfunction "2_2") (pintype "passive"))
    )
    (net (code "43") (name "Net-(U7B--)") (class "Default")
      (node (ref "D22") (pin "3") (pinfunction "A_3") (pintype "passive"))
      (node (ref "R31") (pin "1") (pintype "passive"))
      (node (ref "U7") (pin "6") (pinfunction "-_6") (pintype "passive"))
      (node (ref "U7") (pin "7") (pinfunction "O_7") (pintype "passive"))
    )
    (net (code "44") (name "Net-(U212A--)") (class "Default")
      (node (ref "R250") (pin "1") (pintype "passive"))
      (node (ref "R251") (pin "1") (pintype "passive"))
      (node (ref "U212") (pin "2") (pinfunction "-_2") (pintype "passive"))
    )
    (net (code "45") (name "Net-(U213A-X)") (class "Default")
      (node (ref "R247") (pin "2") (pintype "passive"))
      (node (ref "R248") (pin "1") (pintype "passive"))
      (node (ref "U213") (pin "13") (pinfunction "X_13") (pintype "passive"))
    )
    (net (code "46") (name "Net-(U213A-X0)") (class "Default")
      (node (ref "R247") (pin "1") (pintype "passive"))
      (node (ref "U213") (pin "12") (pinfunction "X0_12") (pintype "passive"))
      (node (ref "VR203") (pin "1") (pinfunction "1_1") (pintype "passive"))
    )
    (net (code "47") (name "Net-(U213A-X1)") (class "Default")
      (node (ref "U213") (pin "1") (pinfunction "Y0_1") (pintype "passive"))
      (node (ref "U213") (pin "14") (pinfunction "X1_14") (pintype "passive"))
    )
    (net (code "48") (name "Net-(U213B-Y2)") (class "Default")
      (node (ref "R248") (pin "2") (pintype "passive"))
      (node (ref "R249") (pin "1") (pintype "passive"))
      (node (ref "U213") (pin "2") (pinfunction "Y2_2") (pintype "passive"))
    )
    (net (code "49") (name "Net-(U218B-+)") (class "Default")
      (node (ref "R293") (pin "2") (pintype "passive"))
      (node (ref "R296") (pin "1") (pintype "passive"))
      (node (ref "U218") (pin "5") (pinfunction "+_5") (pintype "passive"))
    )
    (net (code "50") (name "Net-(U220-CV)") (class "Default")
      (node (ref "C222") (pin "1") (pintype "passive"))
      (node (ref "U220") (pin "5") (pinfunction "CV_5") (pintype "passive"))
    )
    (net (code "51") (name "Net-(U221-CV)") (class "Default")
      (node (ref "C221") (pin "1") (pintype "passive"))
      (node (ref "U221") (pin "5") (pinfunction "CV_5") (pintype "passive"))
    )
    (net (code "52") (name "Net-(U222A-+)") (class "Default")
      (node (ref "C224") (pin "2") (pintype "passive"))
      (node (ref "R301") (pin "2") (pintype "passive"))
      (node (ref "R303") (pin "1") (pintype "passive"))
      (node (ref "R304") (pin "1") (pintype "passive"))
      (node (ref "U222") (pin "3") (pinfunction "+_3") (pintype "passive"))
    )
    (net (code "53") (name "Net-(U222B-+)") (class "Default")
      (node (ref "C225") (pin "2") (pintype "passive"))
      (node (ref "R305") (pin "1") (pintype "passive"))
      (node (ref "R306") (pin "1") (pintype "passive"))
      (node (ref "R307") (pin "2") (pintype "passive"))
      (node (ref "U222") (pin "5") (pinfunction "+_5") (pintype "passive"))
    )
    (net (code "54") (name "P5V") (class "Default")
      (node (ref "C220") (pin "1") (pintype "passive"))
      (node (ref "Q214") (pin "2") (pinfunction "E_2") (pintype "passive"))
      (node (ref "Q216") (pin "3") (pinfunction "C_3") (pintype "passive"))
      (node (ref "R283") (pin "1") (pintype "passive"))
      (node (ref "R286") (pin "1") (pintype "passive"))
      (node (ref "R290") (pin "1") (pintype "passive"))
      (node (ref "R291") (pin "1") (pintype "passive"))
      (node (ref "R293") (pin "1") (pintype "passive"))
      (node (ref "U220") (pin "4") (pinfunction "~{RST}_4") (pintype "passive"))
      (node (ref "U220") (pin "8") (pinfunction "VCC_8") (pintype "passive"))
      (node (ref "U221") (pin "4") (pinfunction "~{RST}_4") (pintype "passive"))
      (node (ref "U221") (pin "8") (pinfunction "VCC_8") (pintype "passive"))
      (node (ref "VR206") (pin "3") (pinfunction "3_3") (pintype "passive"))
    )
    (net (code "55") (name "P15VA") (class "Default")
      (node (ref "D22") (pin "2") (pinfunction "A_2") (pintype "passive"))
    )
    (net (code "56") (name "VREF") (class "Default") (node (ref "R306") (pin "2") (pintype "passive")))
    (net (code "57") (name "unconnected-(U220-DIS-Pad7)") (class "Default")
      (node (ref "U220") (pin "7") (pinfunction "DIS_7") (pintype "passive"))
    )
    (net (code "58") (name "unconnected-(U221-DIS-Pad7)") (class "Default")
      (node (ref "U221") (pin "7") (pinfunction "DIS_7") (pintype "passive"))
    )
  )
)
